# ProPrj__lt_gt__2024-07-21.net
KiCad netlist of a schematic drawn in EasyEDA Pro
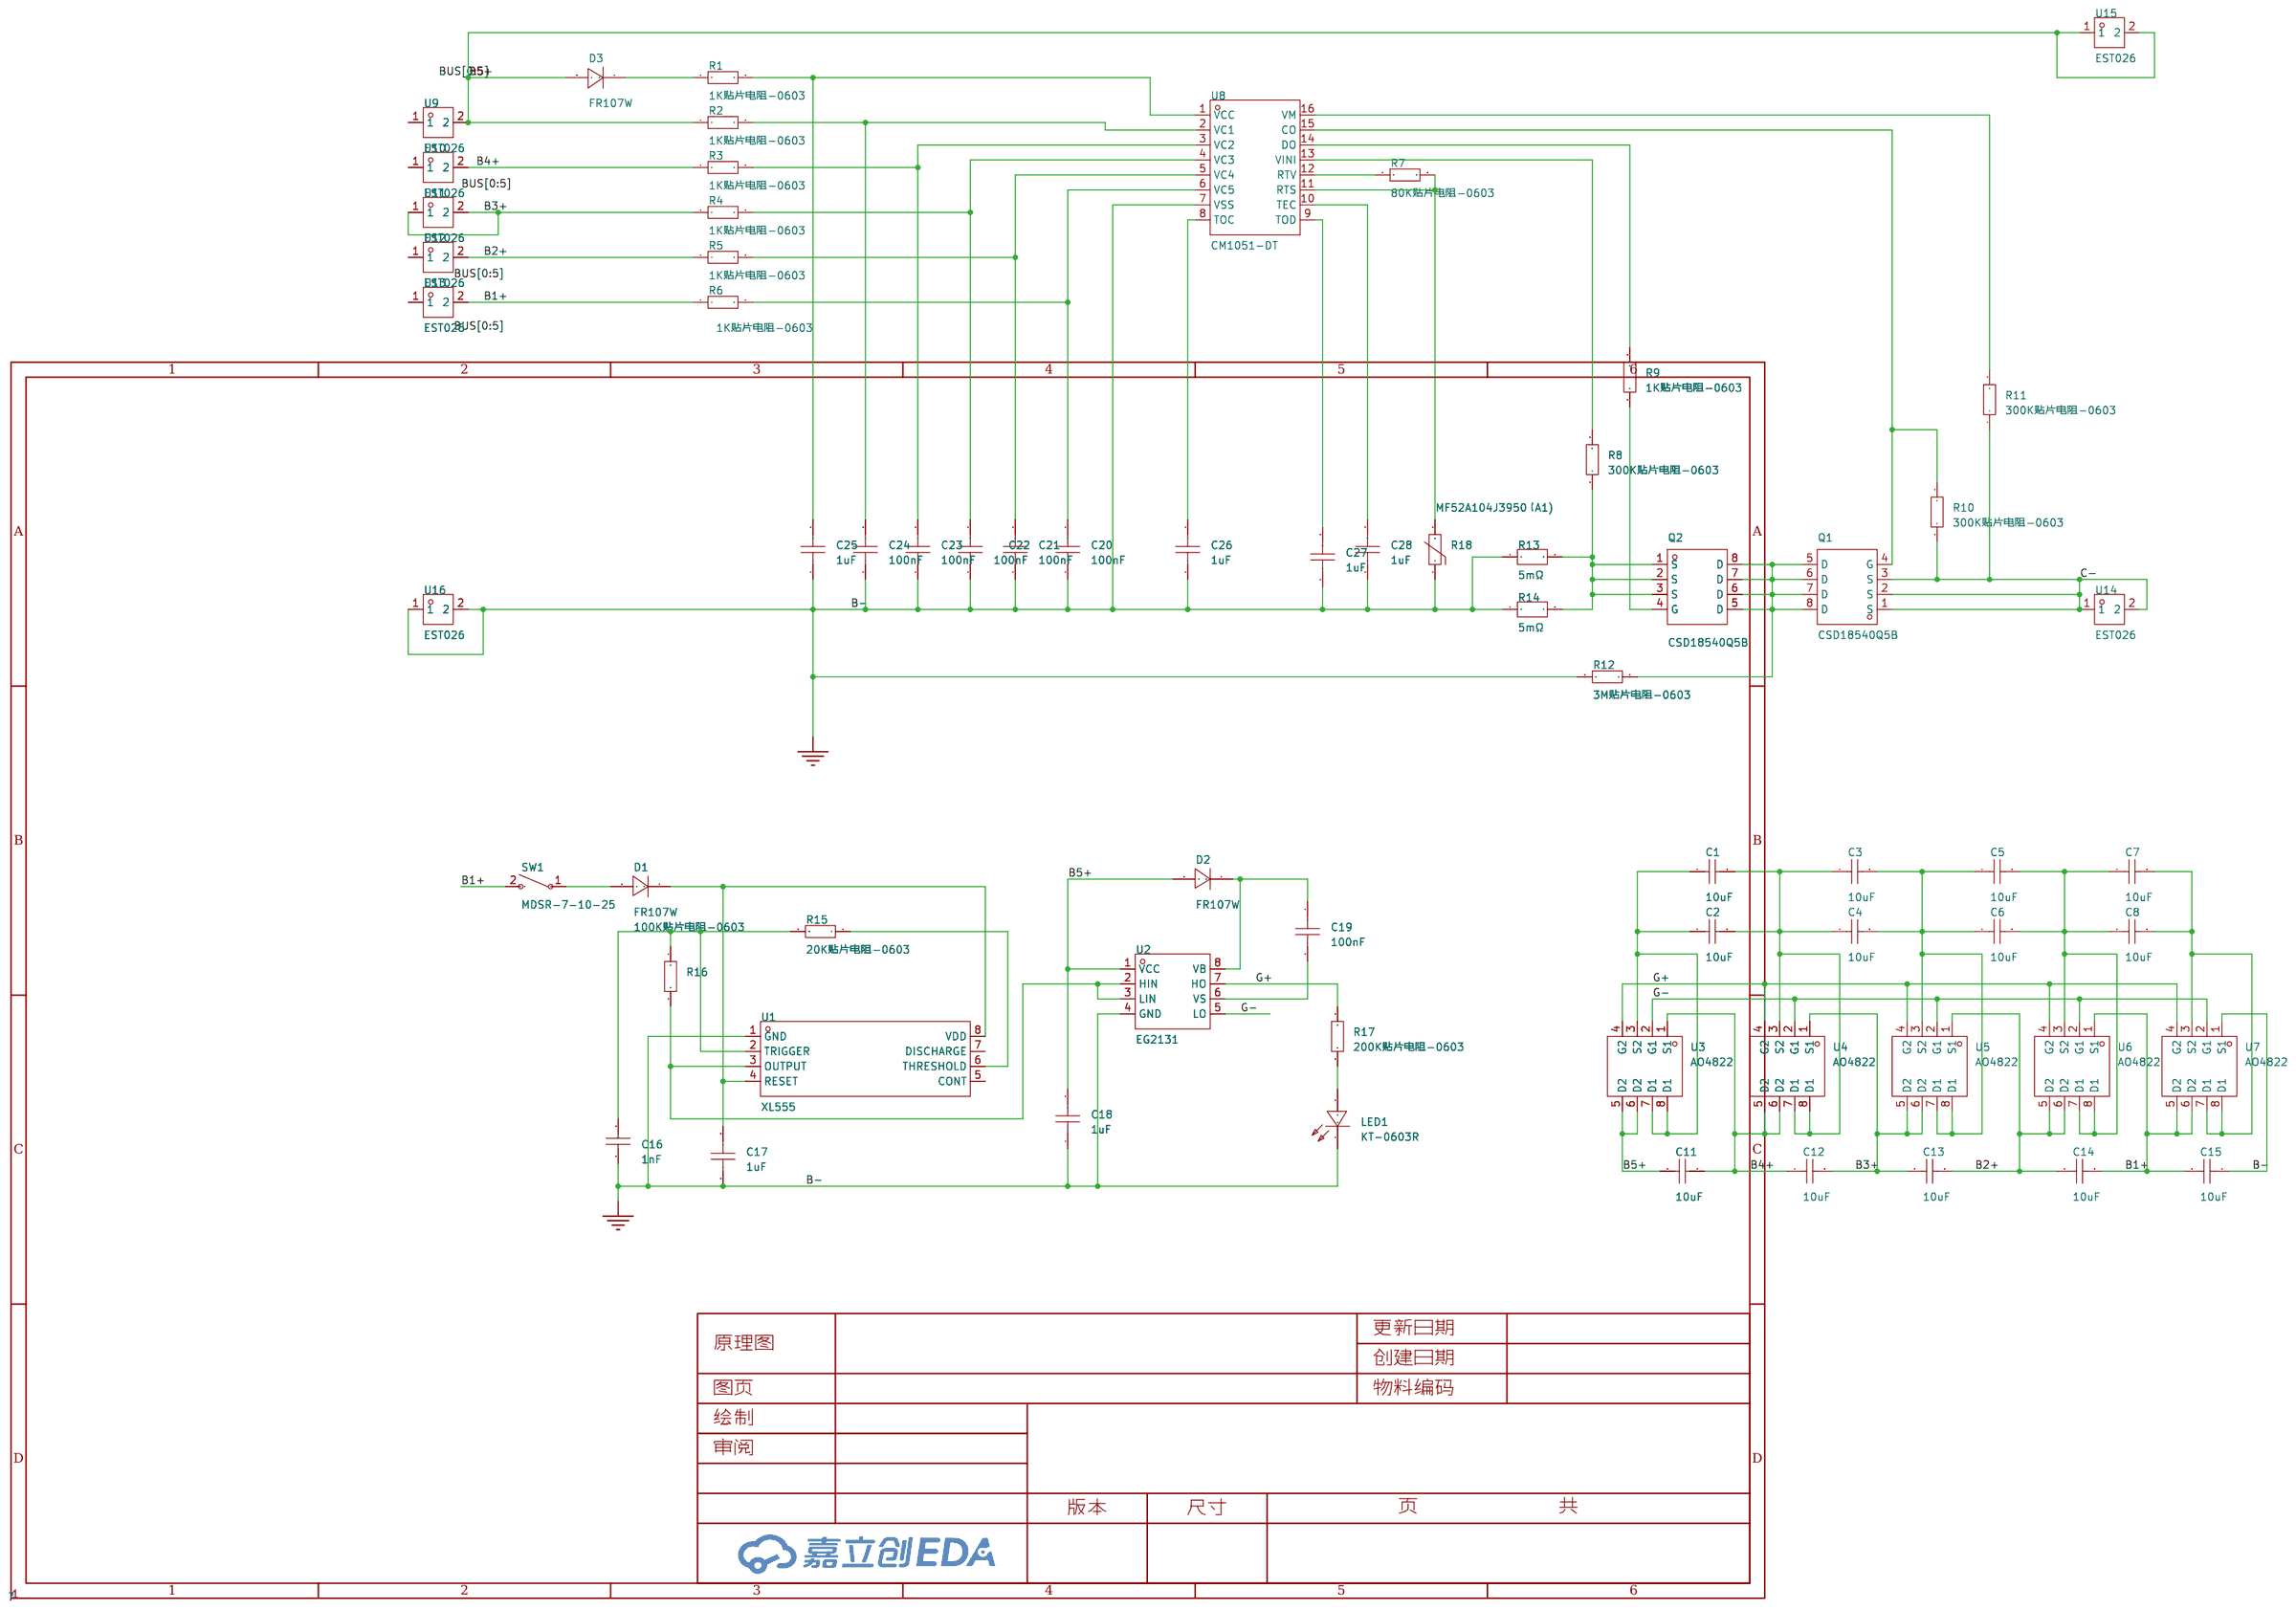
[diagram p0: schematic sheet]

(export (version "E")
  (design (tool "Eeschema 10.0.6"))
  (components
    (comp (ref "C1")
      (value "10uF")
      (footprint "easyedapro:C1206")
      (description "容值:10uF;精度:±10%;额定电压:50V;材质(温度系数):X5R;")
      (fields
        (field (name "Manufacturer Part") "CL31A106KBHNNNE")
        (field (name "Manufacturer") "SAMSUNG(三星)")
      )
      (libsource (lib "easyedapro") (part "CL31A106KBHNNNE"))
    )
    (comp (ref "C2")
      (value "10uF")
      (footprint "easyedapro:C1206")
      (description "容值:10uF;精度:±10%;额定电压:50V;材质(温度系数):X5R;")
      (fields
        (field (name "Manufacturer Part") "CL31A106KBHNNNE")
        (field (name "Manufacturer") "SAMSUNG(三星)")
      )
      (libsource (lib "easyedapro") (part "CL31A106KBHNNNE"))
    )
    (comp (ref "C3")
      (value "10uF")
      (footprint "easyedapro:C1206")
      (description "容值:10uF;精度:±10%;额定电压:50V;材质(温度系数):X5R;")
      (fields
        (field (name "Manufacturer Part") "CL31A106KBHNNNE")
        (field (name "Manufacturer") "SAMSUNG(三星)")
      )
      (libsource (lib "easyedapro") (part "CL31A106KBHNNNE"))
    )
    (comp (ref "C4")
      (value "10uF")
      (footprint "easyedapro:C1206")
      (description "容值:10uF;精度:±10%;额定电压:50V;材质(温度系数):X5R;")
      (fields
        (field (name "Manufacturer Part") "CL31A106KBHNNNE")
        (field (name "Manufacturer") "SAMSUNG(三星)")
      )
      (libsource (lib "easyedapro") (part "CL31A106KBHNNNE"))
    )
    (comp (ref "C5")
      (value "10uF")
      (footprint "easyedapro:C1206")
      (description "容值:10uF;精度:±10%;额定电压:50V;材质(温度系数):X5R;")
      (fields
        (field (name "Manufacturer Part") "CL31A106KBHNNNE")
        (field (name "Manufacturer") "SAMSUNG(三星)")
      )
      (libsource (lib "easyedapro") (part "CL31A106KBHNNNE"))
    )
    (comp (ref "C6")
      (value "10uF")
      (footprint "easyedapro:C1206")
      (description "容值:10uF;精度:±10%;额定电压:50V;材质(温度系数):X5R;")
      (fields
        (field (name "Manufacturer Part") "CL31A106KBHNNNE")
        (field (name "Manufacturer") "SAMSUNG(三星)")
      )
      (libsource (lib "easyedapro") (part "CL31A106KBHNNNE"))
    )
    (comp (ref "C7")
      (value "10uF")
      (footprint "easyedapro:C1206")
      (description "容值:10uF;精度:±10%;额定电压:50V;材质(温度系数):X5R;")
      (fields
        (field (name "Manufacturer Part") "CL31A106KBHNNNE")
        (field (name "Manufacturer") "SAMSUNG(三星)")
      )
      (libsource (lib "easyedapro") (part "CL31A106KBHNNNE"))
    )
    (comp (ref "C8")
      (value "10uF")
      (footprint "easyedapro:C1206")
      (description "容值:10uF;精度:±10%;额定电压:50V;材质(温度系数):X5R;")
      (fields
        (field (name "Manufacturer Part") "CL31A106KBHNNNE")
        (field (name "Manufacturer") "SAMSUNG(三星)")
      )
      (libsource (lib "easyedapro") (part "CL31A106KBHNNNE"))
    )
    (comp (ref "C11")
      (value "10uF")
      (footprint "easyedapro:C1206")
      (description "容值:10uF;精度:±10%;额定电压:50V;材质(温度系数):X5R;")
      (fields
        (field (name "Manufacturer Part") "CL31A106KBHNNNE")
        (field (name "Manufacturer") "SAMSUNG(三星)")
      )
      (libsource (lib "easyedapro") (part "CL31A106KBHNNNE"))
    )
    (comp (ref "C12")
      (value "10uF")
      (footprint "easyedapro:C1206")
      (description "容值:10uF;精度:±10%;额定电压:50V;材质(温度系数):X5R;")
      (fields
        (field (name "Manufacturer Part") "CL31A106KBHNNNE")
        (field (name "Manufacturer") "SAMSUNG(三星)")
      )
      (libsource (lib "easyedapro") (part "CL31A106KBHNNNE"))
    )
    (comp (ref "C13")
      (value "10uF")
      (footprint "easyedapro:C1206")
      (description "容值:10uF;精度:±10%;额定电压:50V;材质(温度系数):X5R;")
      (fields
        (field (name "Manufacturer Part") "CL31A106KBHNNNE")
        (field (name "Manufacturer") "SAMSUNG(三星)")
      )
      (libsource (lib "easyedapro") (part "CL31A106KBHNNNE"))
    )
    (comp (ref "C14")
      (value "10uF")
      (footprint "easyedapro:C1206")
      (description "容值:10uF;精度:±10%;额定电压:50V;材质(温度系数):X5R;")
      (fields
        (field (name "Manufacturer Part") "CL31A106KBHNNNE")
        (field (name "Manufacturer") "SAMSUNG(三星)")
      )
      (libsource (lib "easyedapro") (part "CL31A106KBHNNNE"))
    )
    (comp (ref "C15")
      (value "10uF")
      (footprint "easyedapro:C1206")
      (description "容值:10uF;精度:±10%;额定电压:50V;材质(温度系数):X5R;")
      (fields
        (field (name "Manufacturer Part") "CL31A106KBHNNNE")
        (field (name "Manufacturer") "SAMSUNG(三星)")
      )
      (libsource (lib "easyedapro") (part "CL31A106KBHNNNE"))
    )
    (comp (ref "C16")
      (value "1nF")
      (footprint "easyedapro:C0603")
      (description "容值:1nF;精度:±10%;额定电压:50V;材质(温度系数):X7R;")
      (fields
        (field (name "Manufacturer Part") "CL10B102KB8NNNC")
        (field (name "Manufacturer") "SAMSUNG(三星)")
      )
      (libsource (lib "easyedapro") (part "CL10B102KB8NNNC"))
    )
    (comp (ref "C17")
      (value "1uF")
      (footprint "easyedapro:C0603")
      (description "容值:1uF;精度:±10%;额定电压:50V;材质(温度系数):X5R;")
      (fields
        (field (name "Manufacturer Part") "CL10A105KB8NNNC")
        (field (name "Manufacturer") "SAMSUNG(三星)")
      )
      (libsource (lib "easyedapro") (part "CL10A105KB8NNNC"))
    )
    (comp (ref "C18")
      (value "1uF")
      (footprint "easyedapro:C0603")
      (description "容值:1uF;精度:±10%;额定电压:50V;材质(温度系数):X5R;")
      (fields
        (field (name "Manufacturer Part") "CL10A105KB8NNNC")
        (field (name "Manufacturer") "SAMSUNG(三星)")
      )
      (libsource (lib "easyedapro") (part "CL10A105KB8NNNC"))
    )
    (comp (ref "C19")
      (value "100nF")
      (footprint "easyedapro:C0603")
      (description "容值:100nF;精度:±10%;额定电压:50V;材质(温度系数):X7R;")
      (fields
        (field (name "Manufacturer Part") "CC0603KRX7R9BB104")
        (field (name "Manufacturer") "YAGEO(国巨)")
      )
      (libsource (lib "easyedapro") (part "CC0603KRX7R9BB104"))
    )
    (comp (ref "C20")
      (value "100nF")
      (footprint "easyedapro:C0603")
      (description "容值:100nF;精度:±10%;额定电压:50V;材质(温度系数):X7R;")
      (fields
        (field (name "Manufacturer Part") "CC0603KRX7R9BB104")
        (field (name "Manufacturer") "YAGEO(国巨)")
      )
      (libsource (lib "easyedapro") (part "CC0603KRX7R9BB104"))
    )
    (comp (ref "C21")
      (value "100nF")
      (footprint "easyedapro:C0603")
      (description "容值:100nF;精度:±10%;额定电压:50V;材质(温度系数):X7R;")
      (fields
        (field (name "Manufacturer Part") "CC0603KRX7R9BB104")
        (field (name "Manufacturer") "YAGEO(国巨)")
      )
      (libsource (lib "easyedapro") (part "CC0603KRX7R9BB104"))
    )
    (comp (ref "C22")
      (value "100nF")
      (footprint "easyedapro:C0603")
      (description "容值:100nF;精度:±10%;额定电压:50V;材质(温度系数):X7R;")
      (fields
        (field (name "Manufacturer Part") "CC0603KRX7R9BB104")
        (field (name "Manufacturer") "YAGEO(国巨)")
      )
      (libsource (lib "easyedapro") (part "CC0603KRX7R9BB104"))
    )
    (comp (ref "C23")
      (value "100nF")
      (footprint "easyedapro:C0603")
      (description "容值:100nF;精度:±10%;额定电压:50V;材质(温度系数):X7R;")
      (fields
        (field (name "Manufacturer Part") "CC0603KRX7R9BB104")
        (field (name "Manufacturer") "YAGEO(国巨)")
      )
      (libsource (lib "easyedapro") (part "CC0603KRX7R9BB104"))
    )
    (comp (ref "C24")
      (value "100nF")
      (footprint "easyedapro:C0603")
      (description "容值:100nF;精度:±10%;额定电压:50V;材质(温度系数):X7R;")
      (fields
        (field (name "Manufacturer Part") "CC0603KRX7R9BB104")
        (field (name "Manufacturer") "YAGEO(国巨)")
      )
      (libsource (lib "easyedapro") (part "CC0603KRX7R9BB104"))
    )
    (comp (ref "C25")
      (value "1uF")
      (footprint "easyedapro:C0603")
      (description "容值:100nF;精度:±10%;额定电压:50V;材质(温度系数):X7R;")
      (fields
        (field (name "Manufacturer Part") "CC0603KRX7R9BB104")
        (field (name "Manufacturer") "YAGEO(国巨)")
      )
      (libsource (lib "easyedapro") (part "CC0603KRX7R9BB104"))
    )
    (comp (ref "C26")
      (value "1uF")
      (footprint "easyedapro:C0603")
      (description "容值:100nF;精度:±10%;额定电压:50V;材质(温度系数):X7R;")
      (fields
        (field (name "Manufacturer Part") "CC0603KRX7R9BB104")
        (field (name "Manufacturer") "YAGEO(国巨)")
      )
      (libsource (lib "easyedapro") (part "CC0603KRX7R9BB104"))
    )
    (comp (ref "C27")
      (value "1uF")
      (footprint "easyedapro:C0603")
      (description "容值:100nF;精度:±10%;额定电压:50V;材质(温度系数):X7R;")
      (fields
        (field (name "Manufacturer Part") "CC0603KRX7R9BB104")
        (field (name "Manufacturer") "YAGEO(国巨)")
      )
      (libsource (lib "easyedapro") (part "CC0603KRX7R9BB104"))
    )
    (comp (ref "C28")
      (value "1uF")
      (footprint "easyedapro:C0603")
      (description "容值:100nF;精度:±10%;额定电压:50V;材质(温度系数):X7R;")
      (fields
        (field (name "Manufacturer Part") "CC0603KRX7R9BB104")
        (field (name "Manufacturer") "YAGEO(国巨)")
      )
      (libsource (lib "easyedapro") (part "CC0603KRX7R9BB104"))
    )
    (comp (ref "D1")
      (value "FR107W")
      (footprint "easyedapro:SOD-123F_L2.8-W1.8-LS3.7-RD")
      (description "二极管配置:独立式;正向压降(Vf):1.3V@1A;直流反向耐压(Vr):1kV;平均整流电流(Io):1A;反向恢复时间(trr):500ns;")
      (fields (field (name "Manufacturer") "晶导微电子"))
      (libsource (lib "easyedapro") (part "FR107W_C108820"))
    )
    (comp (ref "D2")
      (value "FR107W")
      (footprint "easyedapro:SOD-123F_L2.8-W1.8-LS3.7-RD")
      (description "二极管配置:独立式;正向压降(Vf):1.3V@1A;直流反向耐压(Vr):1kV;平均整流电流(Io):1A;反向恢复时间(trr):500ns;")
      (fields (field (name "Manufacturer") "晶导微电子"))
      (libsource (lib "easyedapro") (part "FR107W_C108820"))
    )
    (comp (ref "D3")
      (value "FR107W")
      (footprint "easyedapro:SOD-123F_L2.8-W1.8-LS3.7-RD")
      (description "二极管配置:独立式;正向压降(Vf):1.3V@1A;直流反向耐压(Vr):1kV;平均整流电流(Io):1A;反向恢复时间(trr):500ns;")
      (fields (field (name "Manufacturer") "晶导微电子"))
      (libsource (lib "easyedapro") (part "FR107W_C108820"))
    )
    (comp (ref "LED1")
      (value "KT-0603R")
      (footprint "easyedapro:LED0603-RD")
      (description "发光颜色:红色;功率:-;正向电流:-;主波长:-;二极管配置:-;透镜颜色:-;色温:-;发光角度:-;载带方式:-;工作温度:-40°C~+85°C;")
      (fields (field (name "Manufacturer") "KENTO"))
      (libsource (lib "easyedapro") (part "KT-0603R"))
    )
    (comp (ref "Q1")
      (value "CSD18540Q5B")
      (footprint "easyedapro:VSON-CLIP-8_L5.0-W6.0-P1.27-BL")
      (fields (field (name "Manufacturer") "TI(德州仪器)"))
      (libsource (lib "easyedapro") (part "CSD18540Q5B"))
    )
    (comp (ref "Q2")
      (value "CSD18540Q5B")
      (footprint "easyedapro:VSON-CLIP-8_L5.0-W6.0-P1.27-BL")
      (fields (field (name "Manufacturer") "TI(德州仪器)"))
      (libsource (lib "easyedapro") (part "CSD18540Q5B"))
    )
    (comp (ref "R1")
      (value "1K贴片电阻-0603")
      (footprint "easyedapro:R0603")
      (libsource (lib "easyedapro") (part "3.8K贴片电阻-0603"))
    )
    (comp (ref "R2")
      (value "1K贴片电阻-0603")
      (footprint "easyedapro:R0603")
      (libsource (lib "easyedapro") (part "3.8K贴片电阻-0603"))
    )
    (comp (ref "R3")
      (value "1K贴片电阻-0603")
      (footprint "easyedapro:R0603")
      (libsource (lib "easyedapro") (part "3.8K贴片电阻-0603"))
    )
    (comp (ref "R4")
      (value "1K贴片电阻-0603")
      (footprint "easyedapro:R0603")
      (libsource (lib "easyedapro") (part "3.8K贴片电阻-0603"))
    )
    (comp (ref "R5")
      (value "1K贴片电阻-0603")
      (footprint "easyedapro:R0603")
      (libsource (lib "easyedapro") (part "3.8K贴片电阻-0603"))
    )
    (comp (ref "R6")
      (value "1K贴片电阻-0603")
      (footprint "easyedapro:R0603")
      (libsource (lib "easyedapro") (part "3.8K贴片电阻-0603"))
    )
    (comp (ref "R7")
      (value "80K贴片电阻-0603")
      (footprint "easyedapro:R0603")
      (libsource (lib "easyedapro") (part "3.8K贴片电阻-0603"))
    )
    (comp (ref "R8")
      (value "300K贴片电阻-0603")
      (footprint "easyedapro:R0603")
      (libsource (lib "easyedapro") (part "3.8K贴片电阻-0603"))
    )
    (comp (ref "R9")
      (value "1K贴片电阻-0603")
      (footprint "easyedapro:R0603")
      (libsource (lib "easyedapro") (part "3.8K贴片电阻-0603"))
    )
    (comp (ref "R10")
      (value "300K贴片电阻-0603")
      (footprint "easyedapro:R0603")
      (libsource (lib "easyedapro") (part "3.8K贴片电阻-0603"))
    )
    (comp (ref "R11")
      (value "300K贴片电阻-0603")
      (footprint "easyedapro:R0603")
      (libsource (lib "easyedapro") (part "3.8K贴片电阻-0603"))
    )
    (comp (ref "R12")
      (value "3M贴片电阻-0603")
      (footprint "easyedapro:R0603")
      (libsource (lib "easyedapro") (part "3.8K贴片电阻-0603"))
    )
    (comp (ref "R13")
      (value "5mΩ")
      (footprint "easyedapro:RES-SMD_L6.4-W3.2-R2512")
      (description "电阻类型:-;阻值:5mΩ;精度:±1%;功率:2W;最大工作电压:-;温度系数:±50ppm/°C;")
      (fields (field (name "Manufacturer Part") "HQR2512R005W2A1"))
      (libsource (lib "easyedapro") (part "HQR2512R005W2A1"))
    )
    (comp (ref "R14")
      (value "5mΩ")
      (footprint "easyedapro:RES-SMD_L6.4-W3.2-R2512")
      (description "电阻类型:-;阻值:5mΩ;精度:±1%;功率:2W;最大工作电压:-;温度系数:±50ppm/°C;")
      (fields (field (name "Manufacturer Part") "HQR2512R005W2A1"))
      (libsource (lib "easyedapro") (part "HQR2512R005W2A1"))
    )
    (comp (ref "R15")
      (value "20K贴片电阻-0603")
      (footprint "easyedapro:R0603")
      (libsource (lib "easyedapro") (part "3.8K贴片电阻-0603"))
    )
    (comp (ref "R16")
      (value "100K贴片电阻-0603")
      (footprint "easyedapro:R0603")
      (libsource (lib "easyedapro") (part "3.8K贴片电阻-0603"))
    )
    (comp (ref "R17")
      (value "200K贴片电阻-0603")
      (footprint "easyedapro:R0603")
      (libsource (lib "easyedapro") (part "3.8K贴片电阻-0603"))
    )
    (comp (ref "R18")
      (value "MF52A104J3950（A1)")
      (footprint "easyedapro:RES-TH_L2.5-W2.5-P1.70-D0.3")
      (description "阻值(25°C):100kΩ;B值(25°C/50°C):3950K;电阻精度:±5%;功率:50mW;B值精度:±1%;最大稳态电流(25°C):-;")
      (fields (field (name "Manufacturer") "时恒"))
      (libsource (lib "easyedapro") (part "100KΩ ±5%_MF52A1"))
    )
    (comp (ref "SW1")
      (value "MDSR-7-10-25")
      (footprint "easyedapro:SW-TH_L12.7-W1.8-P17.7-L")
      (fields (field (name "Manufacturer") "Littelfuse(美国力特)"))
      (libsource (lib "easyedapro") (part "MDSR-7-10-25"))
    )
    (comp (ref "U1")
      (value "XL555")
      (footprint "easyedapro:SOP-8_L5.0-W4.0-P1.27-LS6.0-BL")
      (description "计时器/振荡器(单路) 频率：2.1MHz 工作电压：2V~15V 工作电流：360uA  2.1MHz、250μA、低功耗计时器")
      (fields (field (name "Manufacturer") "XINLUDA(信路达)"))
      (libsource (lib "easyedapro") (part "XL555"))
    )
    (comp (ref "U2")
      (value "EG2131")
      (footprint "easyedapro:SOP-8_L4.9-W3.9-P1.27-LS6.0-BL")
      (fields (field (name "Manufacturer") "EG(屹晶微)"))
      (libsource (lib "easyedapro") (part "EG2131_C5240691"))
    )
    (comp (ref "U3")
      (value "AO4822")
      (footprint "easyedapro:SOP-8_L5.1-W3.9-P1.27-LS6.0-BL")
      (description "类型:2个N沟道;漏源电压(Vdss):30V;连续漏极电流(Id):8A;功率(Pd):2W;导通电阻(RDS(on)@Vgs,Id):19mΩ@10V,8A;")
      (fields (field (name "Manufacturer") "JSMSEMI(杰盛微)"))
      (libsource (lib "easyedapro") (part "AO4822"))
    )
    (comp (ref "U4")
      (value "AO4822")
      (footprint "easyedapro:SOP-8_L5.1-W3.9-P1.27-LS6.0-BL")
      (description "类型:2个N沟道;漏源电压(Vdss):30V;连续漏极电流(Id):8A;功率(Pd):2W;导通电阻(RDS(on)@Vgs,Id):19mΩ@10V,8A;")
      (fields (field (name "Manufacturer") "JSMSEMI(杰盛微)"))
      (libsource (lib "easyedapro") (part "AO4822"))
    )
    (comp (ref "U5")
      (value "AO4822")
      (footprint "easyedapro:SOP-8_L5.1-W3.9-P1.27-LS6.0-BL")
      (description "类型:2个N沟道;漏源电压(Vdss):30V;连续漏极电流(Id):8A;功率(Pd):2W;导通电阻(RDS(on)@Vgs,Id):19mΩ@10V,8A;")
      (fields (field (name "Manufacturer") "JSMSEMI(杰盛微)"))
      (libsource (lib "easyedapro") (part "AO4822"))
    )
    (comp (ref "U6")
      (value "AO4822")
      (footprint "easyedapro:SOP-8_L5.1-W3.9-P1.27-LS6.0-BL")
      (description "类型:2个N沟道;漏源电压(Vdss):30V;连续漏极电流(Id):8A;功率(Pd):2W;导通电阻(RDS(on)@Vgs,Id):19mΩ@10V,8A;")
      (fields (field (name "Manufacturer") "JSMSEMI(杰盛微)"))
      (libsource (lib "easyedapro") (part "AO4822"))
    )
    (comp (ref "U7")
      (value "AO4822")
      (footprint "easyedapro:SOP-8_L5.1-W3.9-P1.27-LS6.0-BL")
      (description "类型:2个N沟道;漏源电压(Vdss):30V;连续漏极电流(Id):8A;功率(Pd):2W;导通电阻(RDS(on)@Vgs,Id):19mΩ@10V,8A;")
      (fields (field (name "Manufacturer") "JSMSEMI(杰盛微)"))
      (libsource (lib "easyedapro") (part "AO4822"))
    )
    (comp (ref "U8")
      (value "CM1051-DT")
      (footprint "easyedapro:TSSOP-16_L5.0-W4.4-P0.64-LS6.4-BL")
      (fields (field (name "Manufacturer") "iCM(创芯微)"))
      (libsource (lib "easyedapro") (part "CM1051-DT"))
    )
    (comp (ref "U9")
      (value "EST026")
      (footprint "easyedapro:CONN-TH_L6.3-W0.8-EST026")
      (description "环保")
      (fields (field (name "Manufacturer") "xcfuse(旭程)"))
      (libsource (lib "easyedapro") (part "EST026"))
    )
    (comp (ref "U10")
      (value "EST026")
      (footprint "easyedapro:CONN-TH_L6.3-W0.8-EST026")
      (description "环保")
      (fields (field (name "Manufacturer") "xcfuse(旭程)"))
      (libsource (lib "easyedapro") (part "EST026"))
    )
    (comp (ref "U11")
      (value "EST026")
      (footprint "easyedapro:CONN-TH_L6.3-W0.8-EST026")
      (description "环保")
      (fields (field (name "Manufacturer") "xcfuse(旭程)"))
      (libsource (lib "easyedapro") (part "EST026"))
    )
    (comp (ref "U12")
      (value "EST026")
      (footprint "easyedapro:CONN-TH_L6.3-W0.8-EST026")
      (description "环保")
      (fields (field (name "Manufacturer") "xcfuse(旭程)"))
      (libsource (lib "easyedapro") (part "EST026"))
    )
    (comp (ref "U13")
      (value "EST026")
      (footprint "easyedapro:CONN-TH_L6.3-W0.8-EST026")
      (description "环保")
      (fields (field (name "Manufacturer") "xcfuse(旭程)"))
      (libsource (lib "easyedapro") (part "EST026"))
    )
    (comp (ref "U14")
      (value "EST026")
      (footprint "easyedapro:CONN-TH_L6.3-W0.8-EST026")
      (description "环保")
      (fields (field (name "Manufacturer") "xcfuse(旭程)"))
      (libsource (lib "easyedapro") (part "EST026"))
    )
    (comp (ref "U15")
      (value "EST026")
      (footprint "easyedapro:CONN-TH_L6.3-W0.8-EST026")
      (description "环保")
      (fields (field (name "Manufacturer") "xcfuse(旭程)"))
      (libsource (lib "easyedapro") (part "EST026"))
    )
    (comp (ref "U16")
      (value "EST026")
      (footprint "easyedapro:CONN-TH_L6.3-W0.8-EST026")
      (description "环保")
      (fields (field (name "Manufacturer") "xcfuse(旭程)"))
      (libsource (lib "easyedapro") (part "EST026"))
    )
  )
  (nets
    (net (code "1") (name "/B1+") (class "Default")
      (node (ref "C14") (pin "2") (pinfunction "2_2") (pintype "input"))
      (node (ref "C15") (pin "1") (pinfunction "1_1") (pintype "input"))
      (node (ref "R6") (pin "1") (pinfunction "1_1") (pintype "unspecified"))
      (node (ref "SW1") (pin "2") (pinfunction "2_2") (pintype "unspecified"))
      (node (ref "U13") (pin "2") (pinfunction "2_2") (pintype "unspecified"))
      (node (ref "U6") (pin "1") (pinfunction "S1_1") (pintype "unspecified"))
      (node (ref "U7") (pin "5") (pinfunction "D2_5") (pintype "unspecified"))
      (node (ref "U7") (pin "6") (pinfunction "D2_6") (pintype "unspecified"))
    )
    (net (code "2") (name "/B2+") (class "Default")
      (node (ref "C13") (pin "2") (pinfunction "2_2") (pintype "input"))
      (node (ref "C14") (pin "1") (pinfunction "1_1") (pintype "input"))
      (node (ref "R5") (pin "1") (pinfunction "1_1") (pintype "unspecified"))
      (node (ref "U12") (pin "2") (pinfunction "2_2") (pintype "unspecified"))
      (node (ref "U5") (pin "1") (pinfunction "S1_1") (pintype "unspecified"))
      (node (ref "U6") (pin "5") (pinfunction "D2_5") (pintype "unspecified"))
      (node (ref "U6") (pin "6") (pinfunction "D2_6") (pintype "unspecified"))
    )
    (net (code "3") (name "/B3+") (class "Default")
      (node (ref "C12") (pin "2") (pinfunction "2_2") (pintype "input"))
      (node (ref "C13") (pin "1") (pinfunction "1_1") (pintype "input"))
      (node (ref "R4") (pin "1") (pinfunction "1_1") (pintype "unspecified"))
      (node (ref "U11") (pin "1") (pinfunction "1_1") (pintype "unspecified"))
      (node (ref "U11") (pin "2") (pinfunction "2_2") (pintype "unspecified"))
      (node (ref "U4") (pin "1") (pinfunction "S1_1") (pintype "unspecified"))
      (node (ref "U5") (pin "5") (pinfunction "D2_5") (pintype "unspecified"))
      (node (ref "U5") (pin "6") (pinfunction "D2_6") (pintype "unspecified"))
    )
    (net (code "4") (name "/B4+") (class "Default")
      (node (ref "C11") (pin "2") (pinfunction "2_2") (pintype "input"))
      (node (ref "C12") (pin "1") (pinfunction "1_1") (pintype "input"))
      (node (ref "R3") (pin "1") (pinfunction "1_1") (pintype "unspecified"))
      (node (ref "U10") (pin "2") (pinfunction "2_2") (pintype "unspecified"))
      (node (ref "U3") (pin "1") (pinfunction "S1_1") (pintype "unspecified"))
      (node (ref "U4") (pin "5") (pinfunction "D2_5") (pintype "unspecified"))
      (node (ref "U4") (pin "6") (pinfunction "D2_6") (pintype "unspecified"))
    )
    (net (code "5") (name "/B5+") (class "Default")
      (node (ref "C11") (pin "1") (pinfunction "1_1") (pintype "input"))
      (node (ref "C18") (pin "2") (pinfunction "2_2") (pintype "unspecified"))
      (node (ref "D2") (pin "2") (pinfunction "A_2") (pintype "unspecified"))
      (node (ref "D3") (pin "2") (pinfunction "A_2") (pintype "unspecified"))
      (node (ref "R2") (pin "1") (pinfunction "1_1") (pintype "unspecified"))
      (node (ref "U15") (pin "1") (pinfunction "1_1") (pintype "unspecified"))
      (node (ref "U15") (pin "2") (pinfunction "2_2") (pintype "unspecified"))
      (node (ref "U2") (pin "1") (pinfunction "VCC_1") (pintype "unspecified"))
      (node (ref "U3") (pin "5") (pinfunction "D2_5") (pintype "unspecified"))
      (node (ref "U3") (pin "6") (pinfunction "D2_6") (pintype "unspecified"))
      (node (ref "U9") (pin "2") (pinfunction "2_2") (pintype "unspecified"))
    )
    (net (code "7") (name "/C-") (class "Default")
      (node (ref "Q1") (pin "1") (pinfunction "S_1") (pintype "unspecified"))
      (node (ref "Q1") (pin "2") (pinfunction "S_2") (pintype "unspecified"))
      (node (ref "Q1") (pin "3") (pinfunction "S_3") (pintype "unspecified"))
      (node (ref "R10") (pin "2") (pinfunction "2_2") (pintype "unspecified"))
      (node (ref "R11") (pin "1") (pinfunction "1_1") (pintype "unspecified"))
      (node (ref "U14") (pin "1") (pinfunction "1_1") (pintype "unspecified"))
      (node (ref "U14") (pin "2") (pinfunction "2_2") (pintype "unspecified"))
    )
    (net (code "8") (name "/G+") (class "Default")
      (node (ref "R17") (pin "1") (pinfunction "1_1") (pintype "unspecified"))
      (node (ref "U2") (pin "7") (pinfunction "HO_7") (pintype "unspecified"))
      (node (ref "U3") (pin "4") (pinfunction "G2_4") (pintype "unspecified"))
      (node (ref "U4") (pin "4") (pinfunction "G2_4") (pintype "unspecified"))
      (node (ref "U5") (pin "4") (pinfunction "G2_4") (pintype "unspecified"))
      (node (ref "U6") (pin "4") (pinfunction "G2_4") (pintype "unspecified"))
      (node (ref "U7") (pin "4") (pinfunction "G2_4") (pintype "unspecified"))
    )
    (net (code "9") (name "/G-") (class "Default")
      (node (ref "U2") (pin "5") (pinfunction "LO_5") (pintype "unspecified"))
      (node (ref "U3") (pin "2") (pinfunction "G1_2") (pintype "unspecified"))
      (node (ref "U4") (pin "2") (pinfunction "G1_2") (pintype "unspecified"))
      (node (ref "U5") (pin "2") (pinfunction "G1_2") (pintype "unspecified"))
      (node (ref "U6") (pin "2") (pinfunction "G1_2") (pintype "unspecified"))
      (node (ref "U7") (pin "2") (pinfunction "G1_2") (pintype "unspecified"))
    )
    (net (code "10") (name "B-") (class "Default")
      (node (ref "C15") (pin "2") (pinfunction "2_2") (pintype "input"))
      (node (ref "C16") (pin "1") (pinfunction "1_1") (pintype "input"))
      (node (ref "C17") (pin "1") (pinfunction "1_1") (pintype "unspecified"))
      (node (ref "C18") (pin "1") (pinfunction "1_1") (pintype "unspecified"))
      (node (ref "C20") (pin "1") (pinfunction "1_1") (pintype "unspecified"))
      (node (ref "C21") (pin "1") (pinfunction "1_1") (pintype "unspecified"))
      (node (ref "C22") (pin "1") (pinfunction "1_1") (pintype "unspecified"))
      (node (ref "C23") (pin "1") (pinfunction "1_1") (pintype "unspecified"))
      (node (ref "C24") (pin "1") (pinfunction "1_1") (pintype "unspecified"))
      (node (ref "C25") (pin "1") (pinfunction "1_1") (pintype "unspecified"))
      (node (ref "C26") (pin "1") (pinfunction "1_1") (pintype "unspecified"))
      (node (ref "C27") (pin "1") (pinfunction "1_1") (pintype "unspecified"))
      (node (ref "C28") (pin "1") (pinfunction "1_1") (pintype "unspecified"))
      (node (ref "LED1") (pin "1") (pinfunction "K_1") (pintype "input"))
      (node (ref "R12") (pin "2") (pinfunction "2_2") (pintype "unspecified"))
      (node (ref "R13") (pin "1") (pinfunction "1_1") (pintype "unspecified"))
      (node (ref "R14") (pin "1") (pinfunction "1_1") (pintype "unspecified"))
      (node (ref "R18") (pin "1") (pinfunction "1_1") (pintype "input"))
      (node (ref "U1") (pin "1") (pinfunction "GND_1") (pintype "unspecified"))
      (node (ref "U16") (pin "1") (pinfunction "1_1") (pintype "unspecified"))
      (node (ref "U16") (pin "2") (pinfunction "2_2") (pintype "unspecified"))
      (node (ref "U2") (pin "4") (pinfunction "GND_4") (pintype "unspecified"))
      (node (ref "U7") (pin "1") (pinfunction "S1_1") (pintype "unspecified"))
      (node (ref "U8") (pin "7") (pinfunction "VSS_7") (pintype "input"))
    )
    (net (code "11") (name "Net-(D1-A)") (class "Default")
      (node (ref "D1") (pin "2") (pinfunction "A_2") (pintype "unspecified"))
      (node (ref "SW1") (pin "1") (pinfunction "1_1") (pintype "unspecified"))
    )
    (net (code "12") (name "Net-(D1-C)") (class "Default")
      (node (ref "C17") (pin "2") (pinfunction "2_2") (pintype "unspecified"))
      (node (ref "D1") (pin "1") (pinfunction "C_1") (pintype "unspecified"))
      (node (ref "U1") (pin "4") (pinfunction "RESET_4") (pintype "unspecified"))
      (node (ref "U1") (pin "8") (pinfunction "VDD_8") (pintype "unspecified"))
    )
    (net (code "13") (name "Net-(D2-C)") (class "Default")
      (node (ref "C19") (pin "1") (pinfunction "1_1") (pintype "unspecified"))
      (node (ref "D2") (pin "1") (pinfunction "C_1") (pintype "unspecified"))
      (node (ref "U2") (pin "8") (pinfunction "VB_8") (pintype "unspecified"))
    )
    (net (code "14") (name "Net-(D3-C)") (class "Default")
      (node (ref "D3") (pin "1") (pinfunction "C_1") (pintype "unspecified"))
      (node (ref "R1") (pin "1") (pinfunction "1_1") (pintype "unspecified"))
    )
    (net (code "15") (name "Net-(LED1-A)") (class "Default")
      (node (ref "LED1") (pin "2") (pinfunction "A_2") (pintype "input"))
      (node (ref "R17") (pin "2") (pinfunction "2_2") (pintype "unspecified"))
    )
    (net (code "16") (name "Net-(Q1-D-Pad5)") (class "Default")
      (node (ref "Q1") (pin "5") (pinfunction "D_5") (pintype "unspecified"))
      (node (ref "Q1") (pin "6") (pinfunction "D_6") (pintype "unspecified"))
      (node (ref "Q1") (pin "7") (pinfunction "D_7") (pintype "unspecified"))
      (node (ref "Q1") (pin "8") (pinfunction "D_8") (pintype "unspecified"))
      (node (ref "Q2") (pin "5") (pinfunction "D_5") (pintype "unspecified"))
      (node (ref "Q2") (pin "6") (pinfunction "D_6") (pintype "unspecified"))
      (node (ref "Q2") (pin "7") (pinfunction "D_7") (pintype "unspecified"))
      (node (ref "Q2") (pin "8") (pinfunction "D_8") (pintype "unspecified"))
      (node (ref "R12") (pin "1") (pinfunction "1_1") (pintype "unspecified"))
    )
    (net (code "17") (name "Net-(Q1-G)") (class "Default")
      (node (ref "Q1") (pin "4") (pinfunction "G_4") (pintype "unspecified"))
      (node (ref "R10") (pin "1") (pinfunction "1_1") (pintype "unspecified"))
      (node (ref "U8") (pin "15") (pinfunction "CO_15") (pintype "input"))
    )
    (net (code "18") (name "Net-(Q2-G)") (class "Default")
      (node (ref "Q2") (pin "4") (pinfunction "G_4") (pintype "unspecified"))
      (node (ref "R9") (pin "1") (pinfunction "1_1") (pintype "unspecified"))
    )
    (net (code "19") (name "Net-(Q2-S-Pad1)") (class "Default")
      (node (ref "Q2") (pin "1") (pinfunction "S_1") (pintype "unspecified"))
      (node (ref "Q2") (pin "2") (pinfunction "S_2") (pintype "unspecified"))
      (node (ref "Q2") (pin "3") (pinfunction "S_3") (pintype "unspecified"))
      (node (ref "R13") (pin "2") (pinfunction "2_2") (pintype "unspecified"))
      (node (ref "R14") (pin "2") (pinfunction "2_2") (pintype "unspecified"))
      (node (ref "R8") (pin "1") (pinfunction "1_1") (pintype "unspecified"))
    )
    (net (code "20") (name "Net-(U1-OUTPUT)") (class "Default")
      (node (ref "R16") (pin "2") (pinfunction "2_2") (pintype "unspecified"))
      (node (ref "U1") (pin "3") (pinfunction "OUTPUT_3") (pintype "unspecified"))
      (node (ref "U2") (pin "2") (pinfunction "HIN_2") (pintype "unspecified"))
      (node (ref "U2") (pin "3") (pinfunction "LIN_3") (pintype "unspecified"))
    )
    (net (code "21") (name "Net-(U1-THRESHOLD)") (class "Default")
      (node (ref "R15") (pin "1") (pinfunction "1_1") (pintype "unspecified"))
      (node (ref "U1") (pin "6") (pinfunction "THRESHOLD_6") (pintype "unspecified"))
    )
    (net (code "22") (name "Net-(U1-TRIGGER)") (class "Default")
      (node (ref "C16") (pin "2") (pinfunction "2_2") (pintype "input"))
      (node (ref "R15") (pin "2") (pinfunction "2_2") (pintype "unspecified"))
      (node (ref "R16") (pin "1") (pinfunction "1_1") (pintype "unspecified"))
      (node (ref "U1") (pin "2") (pinfunction "TRIGGER_2") (pintype "unspecified"))
    )
    (net (code "23") (name "Net-(U2-VS)") (class "Default")
      (node (ref "C19") (pin "2") (pinfunction "2_2") (pintype "unspecified"))
      (node (ref "U2") (pin "6") (pinfunction "VS_6") (pintype "unspecified"))
    )
    (net (code "24") (name "Net-(U3-S2)") (class "Default")
      (node (ref "C1") (pin "1") (pinfunction "1_1") (pintype "input"))
      (node (ref "C2") (pin "1") (pinfunction "1_1") (pintype "input"))
      (node (ref "U3") (pin "3") (pinfunction "S2_3") (pintype "unspecified"))
      (node (ref "U3") (pin "7") (pinfunction "D1_7") (pintype "unspecified"))
      (node (ref "U3") (pin "8") (pinfunction "D1_8") (pintype "unspecified"))
    )
    (net (code "25") (name "Net-(U4-S2)") (class "Default")
      (node (ref "C1") (pin "2") (pinfunction "2_2") (pintype "input"))
      (node (ref "C2") (pin "2") (pinfunction "2_2") (pintype "input"))
      (node (ref "C3") (pin "1") (pinfunction "1_1") (pintype "input"))
      (node (ref "C4") (pin "1") (pinfunction "1_1") (pintype "input"))
      (node (ref "U4") (pin "3") (pinfunction "S2_3") (pintype "unspecified"))
      (node (ref "U4") (pin "7") (pinfunction "D1_7") (pintype "unspecified"))
      (node (ref "U4") (pin "8") (pinfunction "D1_8") (pintype "unspecified"))
    )
    (net (code "26") (name "Net-(U5-S2)") (class "Default")
      (node (ref "C3") (pin "2") (pinfunction "2_2") (pintype "input"))
      (node (ref "C4") (pin "2") (pinfunction "2_2") (pintype "input"))
      (node (ref "C5") (pin "1") (pinfunction "1_1") (pintype "input"))
      (node (ref "C6") (pin "1") (pinfunction "1_1") (pintype "input"))
      (node (ref "U5") (pin "3") (pinfunction "S2_3") (pintype "unspecified"))
      (node (ref "U5") (pin "7") (pinfunction "D1_7") (pintype "unspecified"))
      (node (ref "U5") (pin "8") (pinfunction "D1_8") (pintype "unspecified"))
    )
    (net (code "27") (name "Net-(U6-S2)") (class "Default")
      (node (ref "C5") (pin "2") (pinfunction "2_2") (pintype "input"))
      (node (ref "C6") (pin "2") (pinfunction "2_2") (pintype "input"))
      (node (ref "C7") (pin "1") (pinfunction "1_1") (pintype "input"))
      (node (ref "C8") (pin "1") (pinfunction "1_1") (pintype "input"))
      (node (ref "U6") (pin "3") (pinfunction "S2_3") (pintype "unspecified"))
      (node (ref "U6") (pin "7") (pinfunction "D1_7") (pintype "unspecified"))
      (node (ref "U6") (pin "8") (pinfunction "D1_8") (pintype "unspecified"))
    )
    (net (code "28") (name "Net-(U7-S2)") (class "Default")
      (node (ref "C7") (pin "2") (pinfunction "2_2") (pintype "input"))
      (node (ref "C8") (pin "2") (pinfunction "2_2") (pintype "input"))
      (node (ref "U7") (pin "3") (pinfunction "S2_3") (pintype "unspecified"))
      (node (ref "U7") (pin "7") (pinfunction "D1_7") (pintype "unspecified"))
      (node (ref "U7") (pin "8") (pinfunction "D1_8") (pintype "unspecified"))
    )
    (net (code "29") (name "Net-(U8-DO)") (class "Default")
      (node (ref "R9") (pin "2") (pinfunction "2_2") (pintype "unspecified"))
      (node (ref "U8") (pin "14") (pinfunction "DO_14") (pintype "input"))
    )
    (net (code "30") (name "Net-(U8-RTS)") (class "Default")
      (node (ref "R18") (pin "2") (pinfunction "2_2") (pintype "input"))
      (node (ref "R7") (pin "2") (pinfunction "2_2") (pintype "unspecified"))
      (node (ref "U8") (pin "11") (pinfunction "RTS_11") (pintype "input"))
    )
    (net (code "31") (name "Net-(U8-RTV)") (class "Default")
      (node (ref "R7") (pin "1") (pinfunction "1_1") (pintype "unspecified"))
      (node (ref "U8") (pin "12") (pinfunction "RTV_12") (pintype "input"))
    )
    (net (code "32") (name "Net-(U8-TEC)") (class "Default")
      (node (ref "C28") (pin "2") (pinfunction "2_2") (pintype "unspecified"))
      (node (ref "U8") (pin "10") (pinfunction "TEC_10") (pintype "input"))
    )
    (net (code "33") (name "Net-(U8-TOC)") (class "Default")
      (node (ref "C26") (pin "2") (pinfunction "2_2") (pintype "unspecified"))
      (node (ref "U8") (pin "8") (pinfunction "TOC_8") (pintype "input"))
    )
    (net (code "34") (name "Net-(U8-TOD)") (class "Default")
      (node (ref "C27") (pin "2") (pinfunction "2_2") (pintype "unspecified"))
      (node (ref "U8") (pin "9") (pinfunction "TOD_9") (pintype "input"))
    )
    (net (code "35") (name "Net-(U8-VC1)") (class "Default")
      (node (ref "C24") (pin "2") (pinfunction "2_2") (pintype "unspecified"))
      (node (ref "R2") (pin "2") (pinfunction "2_2") (pintype "unspecified"))
      (node (ref "U8") (pin "2") (pinfunction "VC1_2") (pintype "input"))
    )
    (net (code "36") (name "Net-(U8-VC2)") (class "Default")
      (node (ref "C23") (pin "2") (pinfunction "2_2") (pintype "unspecified"))
      (node (ref "R3") (pin "2") (pinfunction "2_2") (pintype "unspecified"))
      (node (ref "U8") (pin "3") (pinfunction "VC2_3") (pintype "input"))
    )
    (net (code "37") (name "Net-(U8-VC3)") (class "Default")
      (node (ref "C22") (pin "2") (pinfunction "2_2") (pintype "unspecified"))
      (node (ref "R4") (pin "2") (pinfunction "2_2") (pintype "unspecified"))
      (node (ref "U8") (pin "4") (pinfunction "VC3_4") (pintype "input"))
    )
    (net (code "38") (name "Net-(U8-VC4)") (class "Default")
      (node (ref "C21") (pin "2") (pinfunction "2_2") (pintype "unspecified"))
      (node (ref "R5") (pin "2") (pinfunction "2_2") (pintype "unspecified"))
      (node (ref "U8") (pin "5") (pinfunction "VC4_5") (pintype "input"))
    )
    (net (code "39") (name "Net-(U8-VC5)") (class "Default")
      (node (ref "C20") (pin "2") (pinfunction "2_2") (pintype "unspecified"))
      (node (ref "R6") (pin "2") (pinfunction "2_2") (pintype "unspecified"))
      (node (ref "U8") (pin "6") (pinfunction "VC5_6") (pintype "input"))
    )
    (net (code "40") (name "Net-(U8-VCC)") (class "Default")
      (node (ref "C25") (pin "2") (pinfunction "2_2") (pintype "unspecified"))
      (node (ref "R1") (pin "2") (pinfunction "2_2") (pintype "unspecified"))
      (node (ref "U8") (pin "1") (pinfunction "VCC_1") (pintype "input"))
    )
    (net (code "41") (name "Net-(U8-VINI)") (class "Default")
      (node (ref "R8") (pin "2") (pinfunction "2_2") (pintype "unspecified"))
      (node (ref "U8") (pin "13") (pinfunction "VINI_13") (pintype "input"))
    )
    (net (code "42") (name "Net-(U8-VM)") (class "Default")
      (node (ref "R11") (pin "2") (pinfunction "2_2") (pintype "unspecified"))
      (node (ref "U8") (pin "16") (pinfunction "VM_16") (pintype "input"))
    )
    (net (code "43") (name "unconnected-(U1-CONT-Pad5)") (class "Default")
      (node (ref "U1") (pin "5") (pinfunction "CONT_5") (pintype "unspecified"))
    )
    (net (code "44") (name "unconnected-(U1-DISCHARGE-Pad7)") (class "Default")
      (node (ref "U1") (pin "7") (pinfunction "DISCHARGE_7") (pintype "unspecified"))
    )
    (net (code "45") (name "unconnected-(U9-Pad1)") (class "Default")
      (node (ref "U9") (pin "1") (pinfunction "1_1") (pintype "unspecified"))
    )
    (net (code "46") (name "unconnected-(U10-Pad1)") (class "Default")
      (node (ref "U10") (pin "1") (pinfunction "1_1") (pintype "unspecified"))
    )
    (net (code "47") (name "unconnected-(U12-Pad1)") (class "Default")
      (node (ref "U12") (pin "1") (pinfunction "1_1") (pintype "unspecified"))
    )
    (net (code "48") (name "unconnected-(U13-Pad1)") (class "Default")
      (node (ref "U13") (pin "1") (pinfunction "1_1") (pintype "unspecified"))
    )
  )
)
